# main.net
KiCad netlist of a schematic drawn in Altium Designer
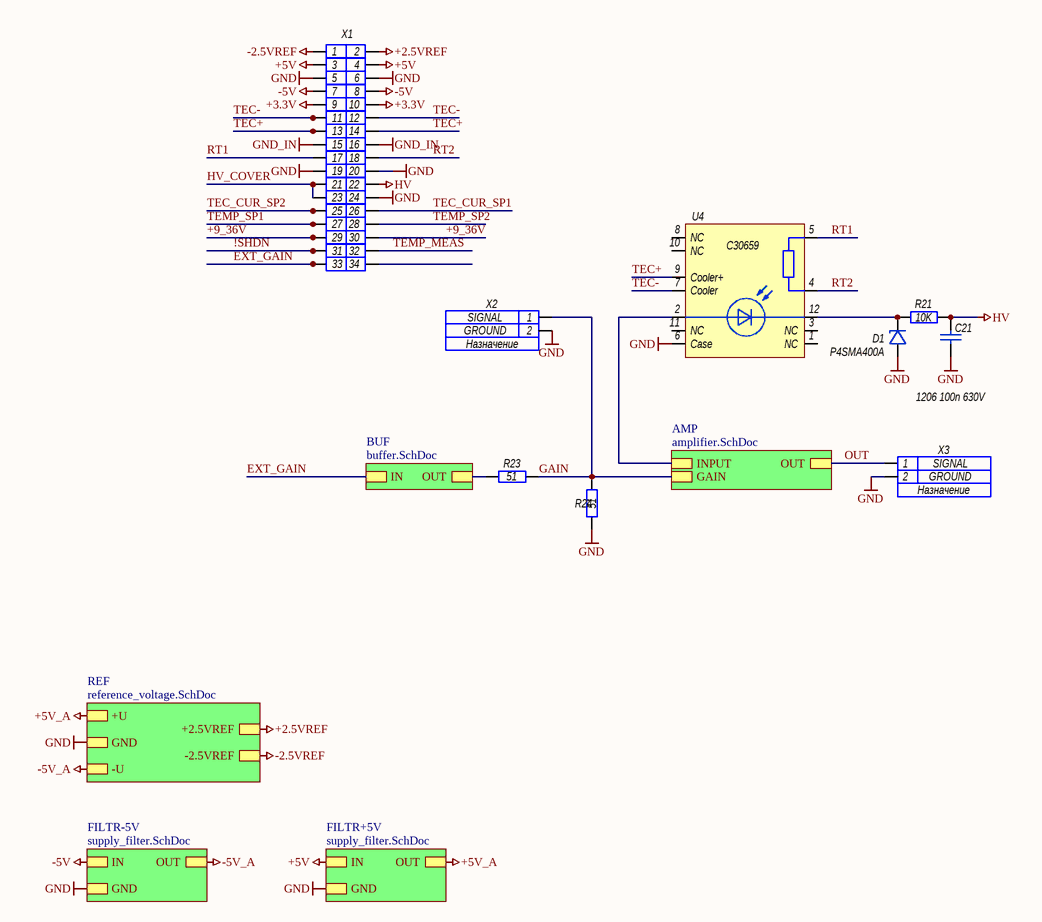
[diagram p0: main.SchDoc]

(export (version "E")
  (design (tool "Eeschema 10.0.6"))
  (components
    (comp (ref "C21")
      (value "1206 100n 630V")
      (footprint "PCB_LIB:CAP_2220")
      (description "Конденсатор")
      (libsource (lib "SCH_LIB") (part "Capacitor"))
    )
    (comp (ref "D1")
      (value "P4SMA400A")
      (footprint "PCB_LIB:SOD-123")
      (description "Диод защитный")
      (libsource (lib "SCH_LIB") (part "SMFxxA"))
    )
    (comp (ref "R21")
      (value "10K")
      (footprint "RES_0805")
      (description "Резистор")
      (libsource (lib "SCH_LIB") (part "Resisitor"))
    )
    (comp (ref "R23")
      (value "51")
      (footprint "RES_0603")
      (description "Резистор")
      (libsource (lib "SCH_LIB") (part "Resisitor"))
    )
    (comp (ref "R24")
      (value "51")
      (footprint "RES_0603")
      (description "Резистор")
      (libsource (lib "SCH_LIB") (part "Resisitor"))
    )
    (comp (ref "U4")
      (value "C30659")
      (footprint "PCB_LIB:C30659")
      (description "Модуль с ЛФД")
      (libsource (lib "SCH_LIB") (part "C30659"))
    )
    (comp (ref "X1") (value "?") (footprint "BH-34") (libsource (lib "SCH_LIB") (part "Connector 17x2")))
    (comp (ref "X2")
      (value "Model")
      (footprint "SMA_V")
      (fields
        (field (name "NET1") "SIGNAL")
        (field (name "NET2") "GROUND")
        (field (name "NAME") "Назначение")
      )
      (libsource (lib "SCH_LIB") (part "Connector 2"))
    )
    (comp (ref "X3")
      (value "Model")
      (footprint "SMA_V")
      (fields
        (field (name "NET1") "SIGNAL")
        (field (name "NET2") "GROUND")
        (field (name "NAME") "Назначение")
      )
      (libsource (lib "SCH_LIB") (part "Connector 2"))
    )
  )
  (nets
    (net (code "1") (name "+2.5VREF") (class "Default")
      (node (ref "X1") (pin "2") (pinfunction "2_2") (pintype "passive"))
    )
    (net (code "2") (name "+3.3V") (class "Default")
      (node (ref "X1") (pin "10") (pinfunction "10_10") (pintype "passive"))
      (node (ref "X1") (pin "9") (pinfunction "9_9") (pintype "passive"))
    )
    (net (code "3") (name "+5V") (class "Default")
      (node (ref "X1") (pin "3") (pinfunction "3_3") (pintype "passive"))
      (node (ref "X1") (pin "4") (pinfunction "4_4") (pintype "passive"))
    )
    (net (code "5") (name "-2.5VREF") (class "Default")
      (node (ref "X1") (pin "1") (pinfunction "1_1") (pintype "passive"))
    )
    (net (code "6") (name "-5V") (class "Default")
      (node (ref "X1") (pin "7") (pinfunction "7_7") (pintype "passive"))
      (node (ref "X1") (pin "8") (pinfunction "8_8") (pintype "passive"))
    )
    (net (code "8") (name "/!SHDN") (class "Default")
      (node (ref "X1") (pin "31") (pinfunction "31_31") (pintype "passive"))
    )
    (net (code "9") (name "/+9_36V") (class "Default")
      (node (ref "X1") (pin "29") (pinfunction "29_29") (pintype "passive"))
      (node (ref "X1") (pin "30") (pinfunction "30_30") (pintype "passive"))
    )
    (net (code "10") (name "/EXT_GAIN") (class "Default")
      (node (ref "X1") (pin "33") (pinfunction "33_33") (pintype "passive"))
    )
    (net (code "11") (name "/GAIN") (class "Default")
      (node (ref "R23") (pin "2") (pinfunction "2_2") (pintype "passive"))
      (node (ref "R24") (pin "2") (pinfunction "2_2") (pintype "passive"))
      (node (ref "X2") (pin "S") (pinfunction "1_S") (pintype "passive"))
    )
    (net (code "12") (name "/HV_COVER") (class "Default")
      (node (ref "X1") (pin "21") (pinfunction "21_21") (pintype "passive"))
      (node (ref "X1") (pin "23") (pinfunction "23_23") (pintype "passive"))
    )
    (net (code "13") (name "/INPUT") (class "Default") (node (ref "U4") (pin "2") (pintype "passive")))
    (net (code "14") (name "/OUT") (class "Default")
      (node (ref "X3") (pin "S") (pinfunction "1_S") (pintype "passive"))
    )
    (net (code "15") (name "/OUT_1") (class "Default")
      (node (ref "R23") (pin "1") (pinfunction "1_1") (pintype "passive"))
    )
    (net (code "16") (name "/RT1") (class "Default")
      (node (ref "U4") (pin "5") (pintype "passive"))
      (node (ref "X1") (pin "17") (pinfunction "17_17") (pintype "passive"))
    )
    (net (code "17") (name "/RT2") (class "Default")
      (node (ref "U4") (pin "4") (pintype "passive"))
      (node (ref "X1") (pin "18") (pinfunction "18_18") (pintype "passive"))
    )
    (net (code "18") (name "/TEC+") (class "Default")
      (node (ref "U4") (pin "9") (pinfunction "Cooler+_9") (pintype "passive"))
      (node (ref "X1") (pin "13") (pinfunction "13_13") (pintype "passive"))
      (node (ref "X1") (pin "14") (pinfunction "14_14") (pintype "passive"))
    )
    (net (code "19") (name "/TEC-") (class "Default")
      (node (ref "U4") (pin "7") (pinfunction "Cooler_7") (pintype "passive"))
      (node (ref "X1") (pin "11") (pinfunction "11_11") (pintype "passive"))
      (node (ref "X1") (pin "12") (pinfunction "12_12") (pintype "passive"))
    )
    (net (code "20") (name "/TEC_CUR_SP1") (class "Default")
      (node (ref "X1") (pin "26") (pinfunction "26_26") (pintype "passive"))
    )
    (net (code "21") (name "/TEC_CUR_SP2") (class "Default")
      (node (ref "X1") (pin "25") (pinfunction "25_25") (pintype "passive"))
    )
    (net (code "22") (name "/TEMP_MEAS") (class "Default")
      (node (ref "X1") (pin "32") (pinfunction "32_32") (pintype "passive"))
    )
    (net (code "23") (name "/TEMP_SP1") (class "Default")
      (node (ref "X1") (pin "27") (pinfunction "27_27") (pintype "passive"))
    )
    (net (code "24") (name "/TEMP_SP2") (class "Default")
      (node (ref "X1") (pin "28") (pinfunction "28_28") (pintype "passive"))
    )
    (net (code "25") (name "GND") (class "Default")
      (node (ref "C21") (pin "2") (pinfunction "2_2") (pintype "passive"))
      (node (ref "D1") (pin "1") (pintype "passive"))
      (node (ref "R24") (pin "1") (pinfunction "1_1") (pintype "passive"))
      (node (ref "U4") (pin "6") (pinfunction "Case_6") (pintype "passive"))
      (node (ref "X1") (pin "19") (pinfunction "19_19") (pintype "passive"))
      (node (ref "X1") (pin "20") (pinfunction "20_20") (pintype "passive"))
      (node (ref "X1") (pin "24") (pinfunction "24_24") (pintype "passive"))
      (node (ref "X1") (pin "5") (pinfunction "5_5") (pintype "passive"))
      (node (ref "X1") (pin "6") (pinfunction "6_6") (pintype "passive"))
      (node (ref "X2") (pin "G") (pinfunction "2_G") (pintype "passive"))
      (node (ref "X3") (pin "G") (pinfunction "2_G") (pintype "passive"))
    )
    (net (code "26") (name "GND_IN") (class "Default")
      (node (ref "X1") (pin "15") (pinfunction "15_15") (pintype "passive"))
      (node (ref "X1") (pin "16") (pinfunction "16_16") (pintype "passive"))
    )
    (net (code "27") (name "HV") (class "Default")
      (node (ref "C21") (pin "1") (pinfunction "1_1") (pintype "passive"))
      (node (ref "R21") (pin "2") (pinfunction "2_2") (pintype "passive"))
      (node (ref "X1") (pin "22") (pinfunction "22_22") (pintype "passive"))
    )
    (net (code "28") (name "Net-(D1-Pad2)") (class "Default")
      (node (ref "D1") (pin "2") (pintype "passive"))
      (node (ref "R21") (pin "1") (pinfunction "1_1") (pintype "passive"))
      (node (ref "U4") (pin "12") (pintype "passive"))
    )
    (net (code "29") (name "unconnected-(U4-NC-Pad1)") (class "Default")
      (node (ref "U4") (pin "1") (pinfunction "NC_1") (pintype "passive"))
    )
    (net (code "30") (name "unconnected-(U4-NC-Pad3)") (class "Default")
      (node (ref "U4") (pin "3") (pinfunction "NC_3") (pintype "passive"))
    )
    (net (code "31") (name "unconnected-(U4-NC-Pad8)") (class "Default")
      (node (ref "U4") (pin "8") (pinfunction "NC_8") (pintype "passive"))
    )
    (net (code "32") (name "unconnected-(U4-NC-Pad10)") (class "Default")
      (node (ref "U4") (pin "10") (pinfunction "NC_10") (pintype "passive"))
    )
    (net (code "33") (name "unconnected-(U4-NC-Pad11)") (class "Default")
      (node (ref "U4") (pin "11") (pinfunction "NC_11") (pintype "passive"))
    )
    (net (code "34") (name "unconnected-(X1-Pad34)") (class "Default")
      (node (ref "X1") (pin "34") (pinfunction "34_34") (pintype "passive"))
    )
  )
)
